# STM32H745.net
KiCad netlist of a schematic drawn in Altium Designer
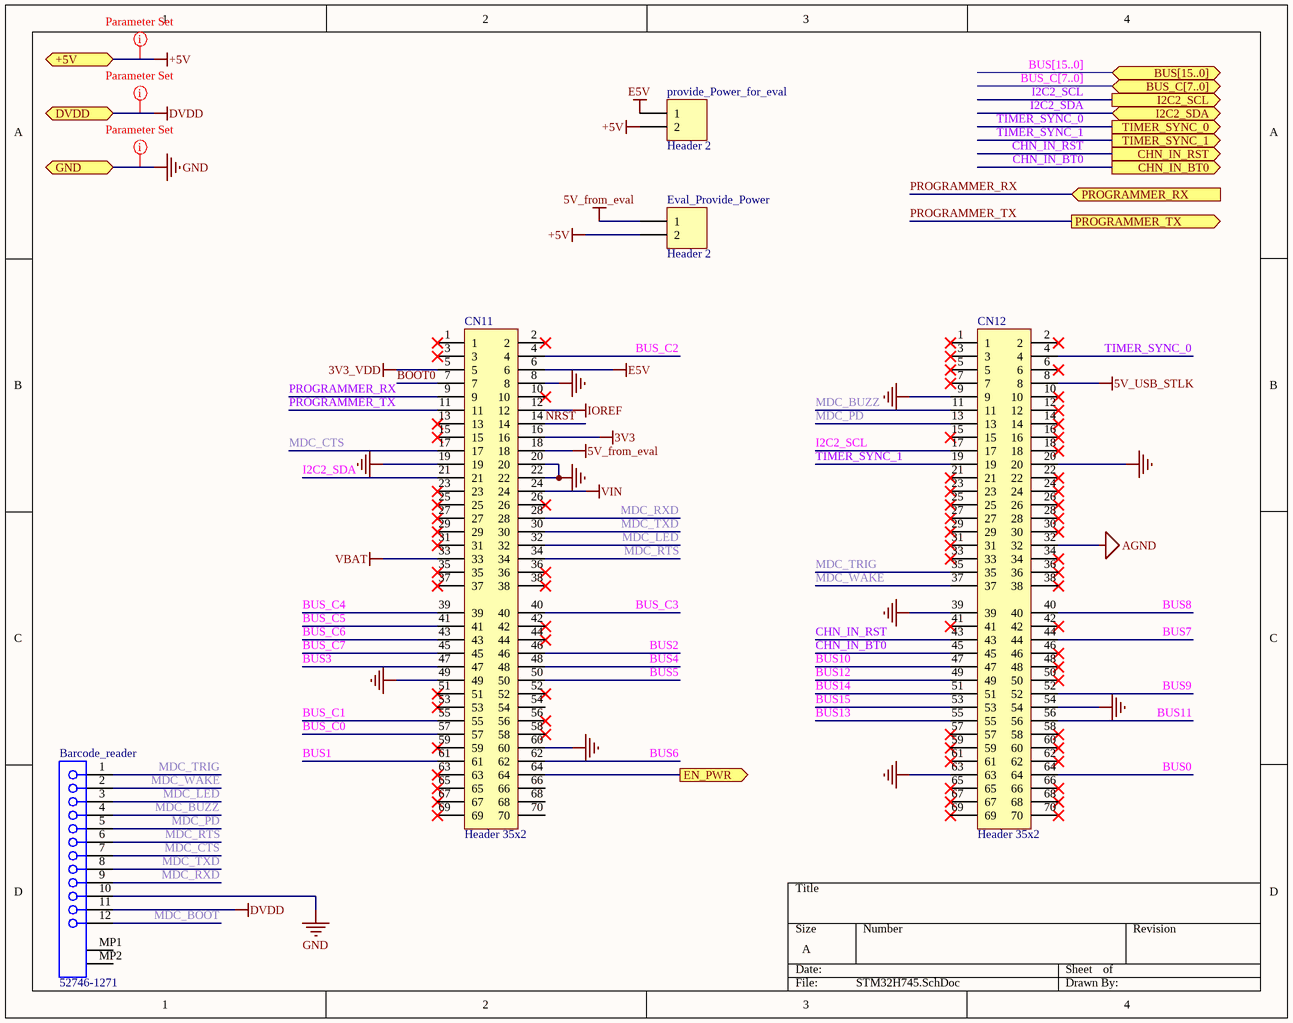
[diagram p0: STM32H745.SchDoc]

(export (version "E")
  (design (tool "Eeschema 10.0.6"))
  (components
    (comp (ref "Barcode_reader")
      (value "52746-1271")
      (footprint "MOLX-52746-1271")
      (fields (field (name "MANUFACTURER") "Molex"))
      (libsource (lib "Altium Content Vault") (part "MOLX-52746-1271"))
    )
    (comp (ref "CN11")
      (value "Header 35x2")
      (footprint "HDR_2x36_2R54_V_M")
      (description "Header, 35x2, 2,54mm, VR, TH, Height 5.84mm/2.54mm")
      (libsource (lib "mantarray_library") (part "MCD-01210"))
    )
    (comp (ref "CN12")
      (value "Header 35x2")
      (footprint "HDR_2x36_2R54_V_M")
      (description "Header, 35x2, 2,54mm, VR, TH, Height 5.84mm/2.54mm")
      (libsource (lib "mantarray_library") (part "MCD-01210"))
    )
    (comp (ref "Eval_Provide_Power")
      (value "Header 2")
      (footprint "HDR1X2")
      (description "Header, 2-Pin")
      (fields (field (name "DIGIKEY_PART_NO") "732-5315-ND") (field (name "PUBLISHER") "Altium Limited"))
      (libsource (lib "Miscellaneous Connectors") (part "Header 2"))
    )
    (comp (ref "provide_Power_for_eval")
      (value "Header 2")
      (footprint "HDR1X2")
      (description "Header, 2-Pin")
      (fields (field (name "DIGIKEY_PART_NO") "732-5315-ND") (field (name "PUBLISHER") "Altium Limited"))
      (libsource (lib "Miscellaneous Connectors") (part "Header 2"))
    )
  )
  (nets
    (net (code "1") (name "+5V") (class "Default")
      (node (ref "Eval_Provide_Power") (pin "2") (pinfunction "2_2") (pintype "passive"))
      (node (ref "provide_Power_for_eval") (pin "2") (pinfunction "2_2") (pintype "passive"))
    )
    (net (code "2") (name "/BOOT0") (class "Default")
      (node (ref "CN11") (pin "7") (pinfunction "7_7") (pintype "passive"))
    )
    (net (code "3") (name "/BUS0") (class "Default")
      (node (ref "CN12") (pin "64") (pinfunction "64_64") (pintype "passive"))
    )
    (net (code "4") (name "/BUS1") (class "Default")
      (node (ref "CN11") (pin "61") (pinfunction "61_61") (pintype "passive"))
    )
    (net (code "5") (name "/BUS2") (class "Default")
      (node (ref "CN11") (pin "46") (pinfunction "46_46") (pintype "passive"))
    )
    (net (code "6") (name "/BUS3") (class "Default")
      (node (ref "CN11") (pin "47") (pinfunction "47_47") (pintype "passive"))
    )
    (net (code "7") (name "/BUS4") (class "Default")
      (node (ref "CN11") (pin "48") (pinfunction "48_48") (pintype "passive"))
    )
    (net (code "8") (name "/BUS5") (class "Default")
      (node (ref "CN11") (pin "50") (pinfunction "50_50") (pintype "passive"))
    )
    (net (code "9") (name "/BUS6") (class "Default")
      (node (ref "CN11") (pin "62") (pinfunction "62_62") (pintype "passive"))
    )
    (net (code "10") (name "/BUS7") (class "Default")
      (node (ref "CN12") (pin "44") (pinfunction "44_44") (pintype "passive"))
    )
    (net (code "11") (name "/BUS8") (class "Default")
      (node (ref "CN12") (pin "40") (pinfunction "40_40") (pintype "passive"))
    )
    (net (code "12") (name "/BUS9") (class "Default")
      (node (ref "CN12") (pin "52") (pinfunction "52_52") (pintype "passive"))
    )
    (net (code "13") (name "/BUS10") (class "Default")
      (node (ref "CN12") (pin "47") (pinfunction "47_47") (pintype "passive"))
    )
    (net (code "14") (name "/BUS11") (class "Default")
      (node (ref "CN12") (pin "56") (pinfunction "56_56") (pintype "passive"))
    )
    (net (code "15") (name "/BUS12") (class "Default")
      (node (ref "CN12") (pin "49") (pinfunction "49_49") (pintype "passive"))
    )
    (net (code "16") (name "/BUS13") (class "Default")
      (node (ref "CN12") (pin "55") (pinfunction "55_55") (pintype "passive"))
    )
    (net (code "17") (name "/BUS14") (class "Default")
      (node (ref "CN12") (pin "51") (pinfunction "51_51") (pintype "passive"))
    )
    (net (code "18") (name "/BUS15") (class "Default")
      (node (ref "CN12") (pin "53") (pinfunction "53_53") (pintype "passive"))
    )
    (net (code "20") (name "/BUS_C0") (class "Default")
      (node (ref "CN11") (pin "57") (pinfunction "57_57") (pintype "passive"))
    )
    (net (code "21") (name "/BUS_C1") (class "Default")
      (node (ref "CN11") (pin "55") (pinfunction "55_55") (pintype "passive"))
    )
    (net (code "22") (name "/BUS_C2") (class "Default")
      (node (ref "CN11") (pin "4") (pinfunction "4_4") (pintype "passive"))
    )
    (net (code "23") (name "/BUS_C3") (class "Default")
      (node (ref "CN11") (pin "40") (pinfunction "40_40") (pintype "passive"))
    )
    (net (code "24") (name "/BUS_C4") (class "Default")
      (node (ref "CN11") (pin "39") (pinfunction "39_39") (pintype "passive"))
    )
    (net (code "25") (name "/BUS_C5") (class "Default")
      (node (ref "CN11") (pin "41") (pinfunction "41_41") (pintype "passive"))
    )
    (net (code "26") (name "/BUS_C6") (class "Default")
      (node (ref "CN11") (pin "43") (pinfunction "43_43") (pintype "passive"))
    )
    (net (code "27") (name "/BUS_C7") (class "Default")
      (node (ref "CN11") (pin "45") (pinfunction "45_45") (pintype "passive"))
    )
    (net (code "29") (name "/CHN_IN_BT0") (class "Default")
      (node (ref "CN12") (pin "45") (pinfunction "45_45") (pintype "passive"))
    )
    (net (code "30") (name "/CHN_IN_RST") (class "Default")
      (node (ref "CN12") (pin "43") (pinfunction "43_43") (pintype "passive"))
    )
    (net (code "31") (name "/EN_PWR") (class "Default")
      (node (ref "CN11") (pin "64") (pinfunction "64_64") (pintype "passive"))
    )
    (net (code "32") (name "/I2C2_SCL") (class "Default")
      (node (ref "CN12") (pin "17") (pinfunction "17_17") (pintype "passive"))
    )
    (net (code "33") (name "/I2C2_SDA") (class "Default")
      (node (ref "CN11") (pin "21") (pinfunction "21_21") (pintype "passive"))
    )
    (net (code "34") (name "/MDC_BOOT") (class "Default")
      (node (ref "Barcode_reader") (pin "12") (pinfunction "12_12") (pintype "passive"))
    )
    (net (code "35") (name "/MDC_BUZZ") (class "Default")
      (node (ref "Barcode_reader") (pin "4") (pinfunction "4_4") (pintype "passive"))
      (node (ref "CN12") (pin "11") (pinfunction "11_11") (pintype "passive"))
    )
    (net (code "36") (name "/MDC_CTS") (class "Default")
      (node (ref "Barcode_reader") (pin "7") (pinfunction "7_7") (pintype "passive"))
      (node (ref "CN11") (pin "17") (pinfunction "17_17") (pintype "passive"))
    )
    (net (code "37") (name "/MDC_LED") (class "Default")
      (node (ref "Barcode_reader") (pin "3") (pinfunction "3_3") (pintype "passive"))
      (node (ref "CN11") (pin "32") (pinfunction "32_32") (pintype "passive"))
    )
    (net (code "38") (name "/MDC_PD") (class "Default")
      (node (ref "Barcode_reader") (pin "5") (pinfunction "5_5") (pintype "passive"))
      (node (ref "CN12") (pin "13") (pinfunction "13_13") (pintype "passive"))
    )
    (net (code "39") (name "/MDC_RTS") (class "Default")
      (node (ref "Barcode_reader") (pin "6") (pinfunction "6_6") (pintype "passive"))
      (node (ref "CN11") (pin "34") (pinfunction "34_34") (pintype "passive"))
    )
    (net (code "40") (name "/MDC_RXD") (class "Default")
      (node (ref "Barcode_reader") (pin "9") (pinfunction "9_9") (pintype "passive"))
      (node (ref "CN11") (pin "28") (pinfunction "28_28") (pintype "passive"))
    )
    (net (code "41") (name "/MDC_TRIG") (class "Default")
      (node (ref "Barcode_reader") (pin "1") (pinfunction "1_1") (pintype "passive"))
      (node (ref "CN12") (pin "35") (pinfunction "35_35") (pintype "passive"))
    )
    (net (code "42") (name "/MDC_TXD") (class "Default")
      (node (ref "Barcode_reader") (pin "8") (pinfunction "8_8") (pintype "passive"))
      (node (ref "CN11") (pin "30") (pinfunction "30_30") (pintype "passive"))
    )
    (net (code "43") (name "/MDC_WAKE") (class "Default")
      (node (ref "Barcode_reader") (pin "2") (pinfunction "2_2") (pintype "passive"))
      (node (ref "CN12") (pin "37") (pinfunction "37_37") (pintype "passive"))
    )
    (net (code "44") (name "/NRST") (class "Default")
      (node (ref "CN11") (pin "14") (pinfunction "14_14") (pintype "passive"))
    )
    (net (code "45") (name "/PROGRAMMER_RX") (class "Default")
      (node (ref "CN11") (pin "9") (pinfunction "9_9") (pintype "passive"))
    )
    (net (code "46") (name "/PROGRAMMER_TX") (class "Default")
      (node (ref "CN11") (pin "11") (pinfunction "11_11") (pintype "passive"))
    )
    (net (code "47") (name "/TIMER_SYNC_0") (class "Default")
      (node (ref "CN12") (pin "4") (pinfunction "4_4") (pintype "passive"))
    )
    (net (code "48") (name "/TIMER_SYNC_1") (class "Default")
      (node (ref "CN12") (pin "19") (pinfunction "19_19") (pintype "passive"))
    )
    (net (code "49") (name "3V3") (class "Default")
      (node (ref "CN11") (pin "16") (pinfunction "16_16") (pintype "passive"))
    )
    (net (code "50") (name "3V3_VDD") (class "Default")
      (node (ref "CN11") (pin "5") (pinfunction "5_5") (pintype "passive"))
    )
    (net (code "51") (name "5V_USB_STLK") (class "Default")
      (node (ref "CN12") (pin "8") (pinfunction "8_8") (pintype "passive"))
    )
    (net (code "52") (name "5V_from_eval") (class "Default")
      (node (ref "CN11") (pin "18") (pinfunction "18_18") (pintype "passive"))
      (node (ref "Eval_Provide_Power") (pin "1") (pinfunction "1_1") (pintype "passive"))
    )
    (net (code "53") (name "AGND") (class "Default")
      (node (ref "CN12") (pin "32") (pinfunction "32_32") (pintype "passive"))
    )
    (net (code "54") (name "DVDD") (class "Default")
      (node (ref "Barcode_reader") (pin "11") (pinfunction "11_11") (pintype "passive"))
    )
    (net (code "55") (name "E5V") (class "Default")
      (node (ref "CN11") (pin "6") (pinfunction "6_6") (pintype "passive"))
      (node (ref "provide_Power_for_eval") (pin "1") (pinfunction "1_1") (pintype "passive"))
    )
    (net (code "56") (name "GND") (class "Default")
      (node (ref "Barcode_reader") (pin "10") (pinfunction "10_10") (pintype "passive"))
      (node (ref "CN11") (pin "19") (pinfunction "19_19") (pintype "passive"))
      (node (ref "CN11") (pin "20") (pinfunction "20_20") (pintype "passive"))
      (node (ref "CN11") (pin "22") (pinfunction "22_22") (pintype "passive"))
      (node (ref "CN11") (pin "49") (pinfunction "49_49") (pintype "passive"))
      (node (ref "CN11") (pin "60") (pinfunction "60_60") (pintype "passive"))
      (node (ref "CN11") (pin "8") (pinfunction "8_8") (pintype "passive"))
      (node (ref "CN12") (pin "20") (pinfunction "20_20") (pintype "passive"))
      (node (ref "CN12") (pin "39") (pinfunction "39_39") (pintype "passive"))
      (node (ref "CN12") (pin "54") (pinfunction "54_54") (pintype "passive"))
      (node (ref "CN12") (pin "63") (pinfunction "63_63") (pintype "passive"))
      (node (ref "CN12") (pin "9") (pinfunction "9_9") (pintype "passive"))
    )
    (net (code "57") (name "IOREF") (class "Default")
      (node (ref "CN11") (pin "12") (pinfunction "12_12") (pintype "passive"))
    )
    (net (code "58") (name "VBAT") (class "Default")
      (node (ref "CN11") (pin "33") (pinfunction "33_33") (pintype "passive"))
    )
    (net (code "59") (name "VIN") (class "Default")
      (node (ref "CN11") (pin "24") (pinfunction "24_24") (pintype "passive"))
    )
    (net (code "60") (name "unconnected-(Barcode_reader-PadMP1)") (class "Default")
      (node (ref "Barcode_reader") (pin "MP1") (pinfunction "MP1_MP1") (pintype "passive"))
    )
    (net (code "61") (name "unconnected-(Barcode_reader-PadMP2)") (class "Default")
      (node (ref "Barcode_reader") (pin "MP2") (pinfunction "MP2_MP2") (pintype "passive"))
    )
    (net (code "62") (name "unconnected-(CN11-Pad1)") (class "Default")
      (node (ref "CN11") (pin "1") (pinfunction "1_1") (pintype "passive+no_connect"))
    )
    (net (code "63") (name "unconnected-(CN11-Pad2)") (class "Default")
      (node (ref "CN11") (pin "2") (pinfunction "2_2") (pintype "passive+no_connect"))
    )
    (net (code "64") (name "unconnected-(CN11-Pad3)") (class "Default")
      (node (ref "CN11") (pin "3") (pinfunction "3_3") (pintype "passive+no_connect"))
    )
    (net (code "65") (name "unconnected-(CN11-Pad10)") (class "Default")
      (node (ref "CN11") (pin "10") (pinfunction "10_10") (pintype "passive+no_connect"))
    )
    (net (code "66") (name "unconnected-(CN11-Pad13)") (class "Default")
      (node (ref "CN11") (pin "13") (pinfunction "13_13") (pintype "passive+no_connect"))
    )
    (net (code "67") (name "unconnected-(CN11-Pad15)") (class "Default")
      (node (ref "CN11") (pin "15") (pinfunction "15_15") (pintype "passive+no_connect"))
    )
    (net (code "68") (name "unconnected-(CN11-Pad23)") (class "Default")
      (node (ref "CN11") (pin "23") (pinfunction "23_23") (pintype "passive+no_connect"))
    )
    (net (code "69") (name "unconnected-(CN11-Pad25)") (class "Default")
      (node (ref "CN11") (pin "25") (pinfunction "25_25") (pintype "passive+no_connect"))
    )
    (net (code "70") (name "unconnected-(CN11-Pad26)") (class "Default")
      (node (ref "CN11") (pin "26") (pinfunction "26_26") (pintype "passive+no_connect"))
    )
    (net (code "71") (name "unconnected-(CN11-Pad27)") (class "Default")
      (node (ref "CN11") (pin "27") (pinfunction "27_27") (pintype "passive+no_connect"))
    )
    (net (code "72") (name "unconnected-(CN11-Pad29)") (class "Default")
      (node (ref "CN11") (pin "29") (pinfunction "29_29") (pintype "passive+no_connect"))
    )
    (net (code "73") (name "unconnected-(CN11-Pad31)") (class "Default")
      (node (ref "CN11") (pin "31") (pinfunction "31_31") (pintype "passive+no_connect"))
    )
    (net (code "74") (name "unconnected-(CN11-Pad35)") (class "Default")
      (node (ref "CN11") (pin "35") (pinfunction "35_35") (pintype "passive+no_connect"))
    )
    (net (code "75") (name "unconnected-(CN11-Pad36)") (class "Default")
      (node (ref "CN11") (pin "36") (pinfunction "36_36") (pintype "passive+no_connect"))
    )
    (net (code "76") (name "unconnected-(CN11-Pad37)") (class "Default")
      (node (ref "CN11") (pin "37") (pinfunction "37_37") (pintype "passive+no_connect"))
    )
    (net (code "77") (name "unconnected-(CN11-Pad38)") (class "Default")
      (node (ref "CN11") (pin "38") (pinfunction "38_38") (pintype "passive+no_connect"))
    )
    (net (code "78") (name "unconnected-(CN11-Pad42)") (class "Default")
      (node (ref "CN11") (pin "42") (pinfunction "42_42") (pintype "passive+no_connect"))
    )
    (net (code "79") (name "unconnected-(CN11-Pad44)") (class "Default")
      (node (ref "CN11") (pin "44") (pinfunction "44_44") (pintype "passive+no_connect"))
    )
    (net (code "80") (name "unconnected-(CN11-Pad51)") (class "Default")
      (node (ref "CN11") (pin "51") (pinfunction "51_51") (pintype "passive+no_connect"))
    )
    (net (code "81") (name "unconnected-(CN11-Pad52)") (class "Default")
      (node (ref "CN11") (pin "52") (pinfunction "52_52") (pintype "passive+no_connect"))
    )
    (net (code "82") (name "unconnected-(CN11-Pad53)") (class "Default")
      (node (ref "CN11") (pin "53") (pinfunction "53_53") (pintype "passive+no_connect"))
    )
    (net (code "83") (name "unconnected-(CN11-Pad54)") (class "Default")
      (node (ref "CN11") (pin "54") (pinfunction "54_54") (pintype "passive"))
    )
    (net (code "84") (name "unconnected-(CN11-Pad56)") (class "Default")
      (node (ref "CN11") (pin "56") (pinfunction "56_56") (pintype "passive+no_connect"))
    )
    (net (code "85") (name "unconnected-(CN11-Pad58)") (class "Default")
      (node (ref "CN11") (pin "58") (pinfunction "58_58") (pintype "passive+no_connect"))
    )
    (net (code "86") (name "unconnected-(CN11-Pad59)") (class "Default")
      (node (ref "CN11") (pin "59") (pinfunction "59_59") (pintype "passive+no_connect"))
    )
    (net (code "87") (name "unconnected-(CN11-Pad63)") (class "Default")
      (node (ref "CN11") (pin "63") (pinfunction "63_63") (pintype "passive+no_connect"))
    )
    (net (code "88") (name "unconnected-(CN11-Pad65)") (class "Default")
      (node (ref "CN11") (pin "65") (pinfunction "65_65") (pintype "passive+no_connect"))
    )
    (net (code "89") (name "unconnected-(CN11-Pad66)") (class "Default")
      (node (ref "CN11") (pin "66") (pinfunction "66_66") (pintype "passive"))
    )
    (net (code "90") (name "unconnected-(CN11-Pad67)") (class "Default")
      (node (ref "CN11") (pin "67") (pinfunction "67_67") (pintype "passive+no_connect"))
    )
    (net (code "91") (name "unconnected-(CN11-Pad68)") (class "Default")
      (node (ref "CN11") (pin "68") (pinfunction "68_68") (pintype "passive"))
    )
    (net (code "92") (name "unconnected-(CN11-Pad69)") (class "Default")
      (node (ref "CN11") (pin "69") (pinfunction "69_69") (pintype "passive+no_connect"))
    )
    (net (code "93") (name "unconnected-(CN11-Pad70)") (class "Default")
      (node (ref "CN11") (pin "70") (pinfunction "70_70") (pintype "passive"))
    )
    (net (code "94") (name "unconnected-(CN12-Pad1)") (class "Default")
      (node (ref "CN12") (pin "1") (pinfunction "1_1") (pintype "passive+no_connect"))
    )
    (net (code "95") (name "unconnected-(CN12-Pad2)") (class "Default")
      (node (ref "CN12") (pin "2") (pinfunction "2_2") (pintype "passive+no_connect"))
    )
    (net (code "96") (name "unconnected-(CN12-Pad3)") (class "Default")
      (node (ref "CN12") (pin "3") (pinfunction "3_3") (pintype "passive+no_connect"))
    )
    (net (code "97") (name "unconnected-(CN12-Pad5)") (class "Default")
      (node (ref "CN12") (pin "5") (pinfunction "5_5") (pintype "passive+no_connect"))
    )
    (net (code "98") (name "unconnected-(CN12-Pad6)") (class "Default")
      (node (ref "CN12") (pin "6") (pinfunction "6_6") (pintype "passive+no_connect"))
    )
    (net (code "99") (name "unconnected-(CN12-Pad7)") (class "Default")
      (node (ref "CN12") (pin "7") (pinfunction "7_7") (pintype "passive+no_connect"))
    )
    (net (code "100") (name "unconnected-(CN12-Pad10)") (class "Default")
      (node (ref "CN12") (pin "10") (pinfunction "10_10") (pintype "passive+no_connect"))
    )
    (net (code "101") (name "unconnected-(CN12-Pad12)") (class "Default")
      (node (ref "CN12") (pin "12") (pinfunction "12_12") (pintype "passive+no_connect"))
    )
    (net (code "102") (name "unconnected-(CN12-Pad14)") (class "Default")
      (node (ref "CN12") (pin "14") (pinfunction "14_14") (pintype "passive+no_connect"))
    )
    (net (code "103") (name "unconnected-(CN12-Pad15)") (class "Default")
      (node (ref "CN12") (pin "15") (pinfunction "15_15") (pintype "passive+no_connect"))
    )
    (net (code "104") (name "unconnected-(CN12-Pad16)") (class "Default")
      (node (ref "CN12") (pin "16") (pinfunction "16_16") (pintype "passive+no_connect"))
    )
    (net (code "105") (name "unconnected-(CN12-Pad18)") (class "Default")
      (node (ref "CN12") (pin "18") (pinfunction "18_18") (pintype "passive+no_connect"))
    )
    (net (code "106") (name "unconnected-(CN12-Pad21)") (class "Default")
      (node (ref "CN12") (pin "21") (pinfunction "21_21") (pintype "passive+no_connect"))
    )
    (net (code "107") (name "unconnected-(CN12-Pad22)") (class "Default")
      (node (ref "CN12") (pin "22") (pinfunction "22_22") (pintype "passive+no_connect"))
    )
    (net (code "108") (name "unconnected-(CN12-Pad23)") (class "Default")
      (node (ref "CN12") (pin "23") (pinfunction "23_23") (pintype "passive+no_connect"))
    )
    (net (code "109") (name "unconnected-(CN12-Pad24)") (class "Default")
      (node (ref "CN12") (pin "24") (pinfunction "24_24") (pintype "passive+no_connect"))
    )
    (net (code "110") (name "unconnected-(CN12-Pad25)") (class "Default")
      (node (ref "CN12") (pin "25") (pinfunction "25_25") (pintype "passive+no_connect"))
    )
    (net (code "111") (name "unconnected-(CN12-Pad26)") (class "Default")
      (node (ref "CN12") (pin "26") (pinfunction "26_26") (pintype "passive+no_connect"))
    )
    (net (code "112") (name "unconnected-(CN12-Pad27)") (class "Default")
      (node (ref "CN12") (pin "27") (pinfunction "27_27") (pintype "passive+no_connect"))
    )
    (net (code "113") (name "unconnected-(CN12-Pad28)") (class "Default")
      (node (ref "CN12") (pin "28") (pinfunction "28_28") (pintype "passive+no_connect"))
    )
    (net (code "114") (name "unconnected-(CN12-Pad29)") (class "Default")
      (node (ref "CN12") (pin "29") (pinfunction "29_29") (pintype "passive+no_connect"))
    )
    (net (code "115") (name "unconnected-(CN12-Pad30)") (class "Default")
      (node (ref "CN12") (pin "30") (pinfunction "30_30") (pintype "passive+no_connect"))
    )
    (net (code "116") (name "unconnected-(CN12-Pad31)") (class "Default")
      (node (ref "CN12") (pin "31") (pinfunction "31_31") (pintype "passive+no_connect"))
    )
    (net (code "117") (name "unconnected-(CN12-Pad33)") (class "Default")
      (node (ref "CN12") (pin "33") (pinfunction "33_33") (pintype "passive+no_connect"))
    )
    (net (code "118") (name "unconnected-(CN12-Pad34)") (class "Default")
      (node (ref "CN12") (pin "34") (pinfunction "34_34") (pintype "passive+no_connect"))
    )
    (net (code "119") (name "unconnected-(CN12-Pad36)") (class "Default")
      (node (ref "CN12") (pin "36") (pinfunction "36_36") (pintype "passive+no_connect"))
    )
    (net (code "120") (name "unconnected-(CN12-Pad38)") (class "Default")
      (node (ref "CN12") (pin "38") (pinfunction "38_38") (pintype "passive+no_connect"))
    )
    (net (code "121") (name "unconnected-(CN12-Pad41)") (class "Default")
      (node (ref "CN12") (pin "41") (pinfunction "41_41") (pintype "passive+no_connect"))
    )
    (net (code "122") (name "unconnected-(CN12-Pad42)") (class "Default")
      (node (ref "CN12") (pin "42") (pinfunction "42_42") (pintype "passive+no_connect"))
    )
    (net (code "123") (name "unconnected-(CN12-Pad46)") (class "Default")
      (node (ref "CN12") (pin "46") (pinfunction "46_46") (pintype "passive+no_connect"))
    )
    (net (code "124") (name "unconnected-(CN12-Pad48)") (class "Default")
      (node (ref "CN12") (pin "48") (pinfunction "48_48") (pintype "passive+no_connect"))
    )
    (net (code "125") (name "unconnected-(CN12-Pad50)") (class "Default")
      (node (ref "CN12") (pin "50") (pinfunction "50_50") (pintype "passive+no_connect"))
    )
    (net (code "126") (name "unconnected-(CN12-Pad57)") (class "Default")
      (node (ref "CN12") (pin "57") (pinfunction "57_57") (pintype "passive+no_connect"))
    )
    (net (code "127") (name "unconnected-(CN12-Pad58)") (class "Default")
      (node (ref "CN12") (pin "58") (pinfunction "58_58") (pintype "passive+no_connect"))
    )
    (net (code "128") (name "unconnected-(CN12-Pad59)") (class "Default")
      (node (ref "CN12") (pin "59") (pinfunction "59_59") (pintype "passive+no_connect"))
    )
    (net (code "129") (name "unconnected-(CN12-Pad60)") (class "Default")
      (node (ref "CN12") (pin "60") (pinfunction "60_60") (pintype "passive+no_connect"))
    )
    (net (code "130") (name "unconnected-(CN12-Pad61)") (class "Default")
      (node (ref "CN12") (pin "61") (pinfunction "61_61") (pintype "passive+no_connect"))
    )
    (net (code "131") (name "unconnected-(CN12-Pad62)") (class "Default")
      (node (ref "CN12") (pin "62") (pinfunction "62_62") (pintype "passive+no_connect"))
    )
    (net (code "132") (name "unconnected-(CN12-Pad65)") (class "Default")
      (node (ref "CN12") (pin "65") (pinfunction "65_65") (pintype "passive+no_connect"))
    )
    (net (code "133") (name "unconnected-(CN12-Pad66)") (class "Default")
      (node (ref "CN12") (pin "66") (pinfunction "66_66") (pintype "passive+no_connect"))
    )
    (net (code "134") (name "unconnected-(CN12-Pad67)") (class "Default")
      (node (ref "CN12") (pin "67") (pinfunction "67_67") (pintype "passive+no_connect"))
    )
    (net (code "135") (name "unconnected-(CN12-Pad68)") (class "Default")
      (node (ref "CN12") (pin "68") (pinfunction "68_68") (pintype "passive+no_connect"))
    )
    (net (code "136") (name "unconnected-(CN12-Pad69)") (class "Default")
      (node (ref "CN12") (pin "69") (pinfunction "69_69") (pintype "passive+no_connect"))
    )
    (net (code "137") (name "unconnected-(CN12-Pad70)") (class "Default")
      (node (ref "CN12") (pin "70") (pinfunction "70_70") (pintype "passive+no_connect"))
    )
  )
)
